# DDR_Memory.net
KiCad netlist of a schematic drawn in Altium Designer
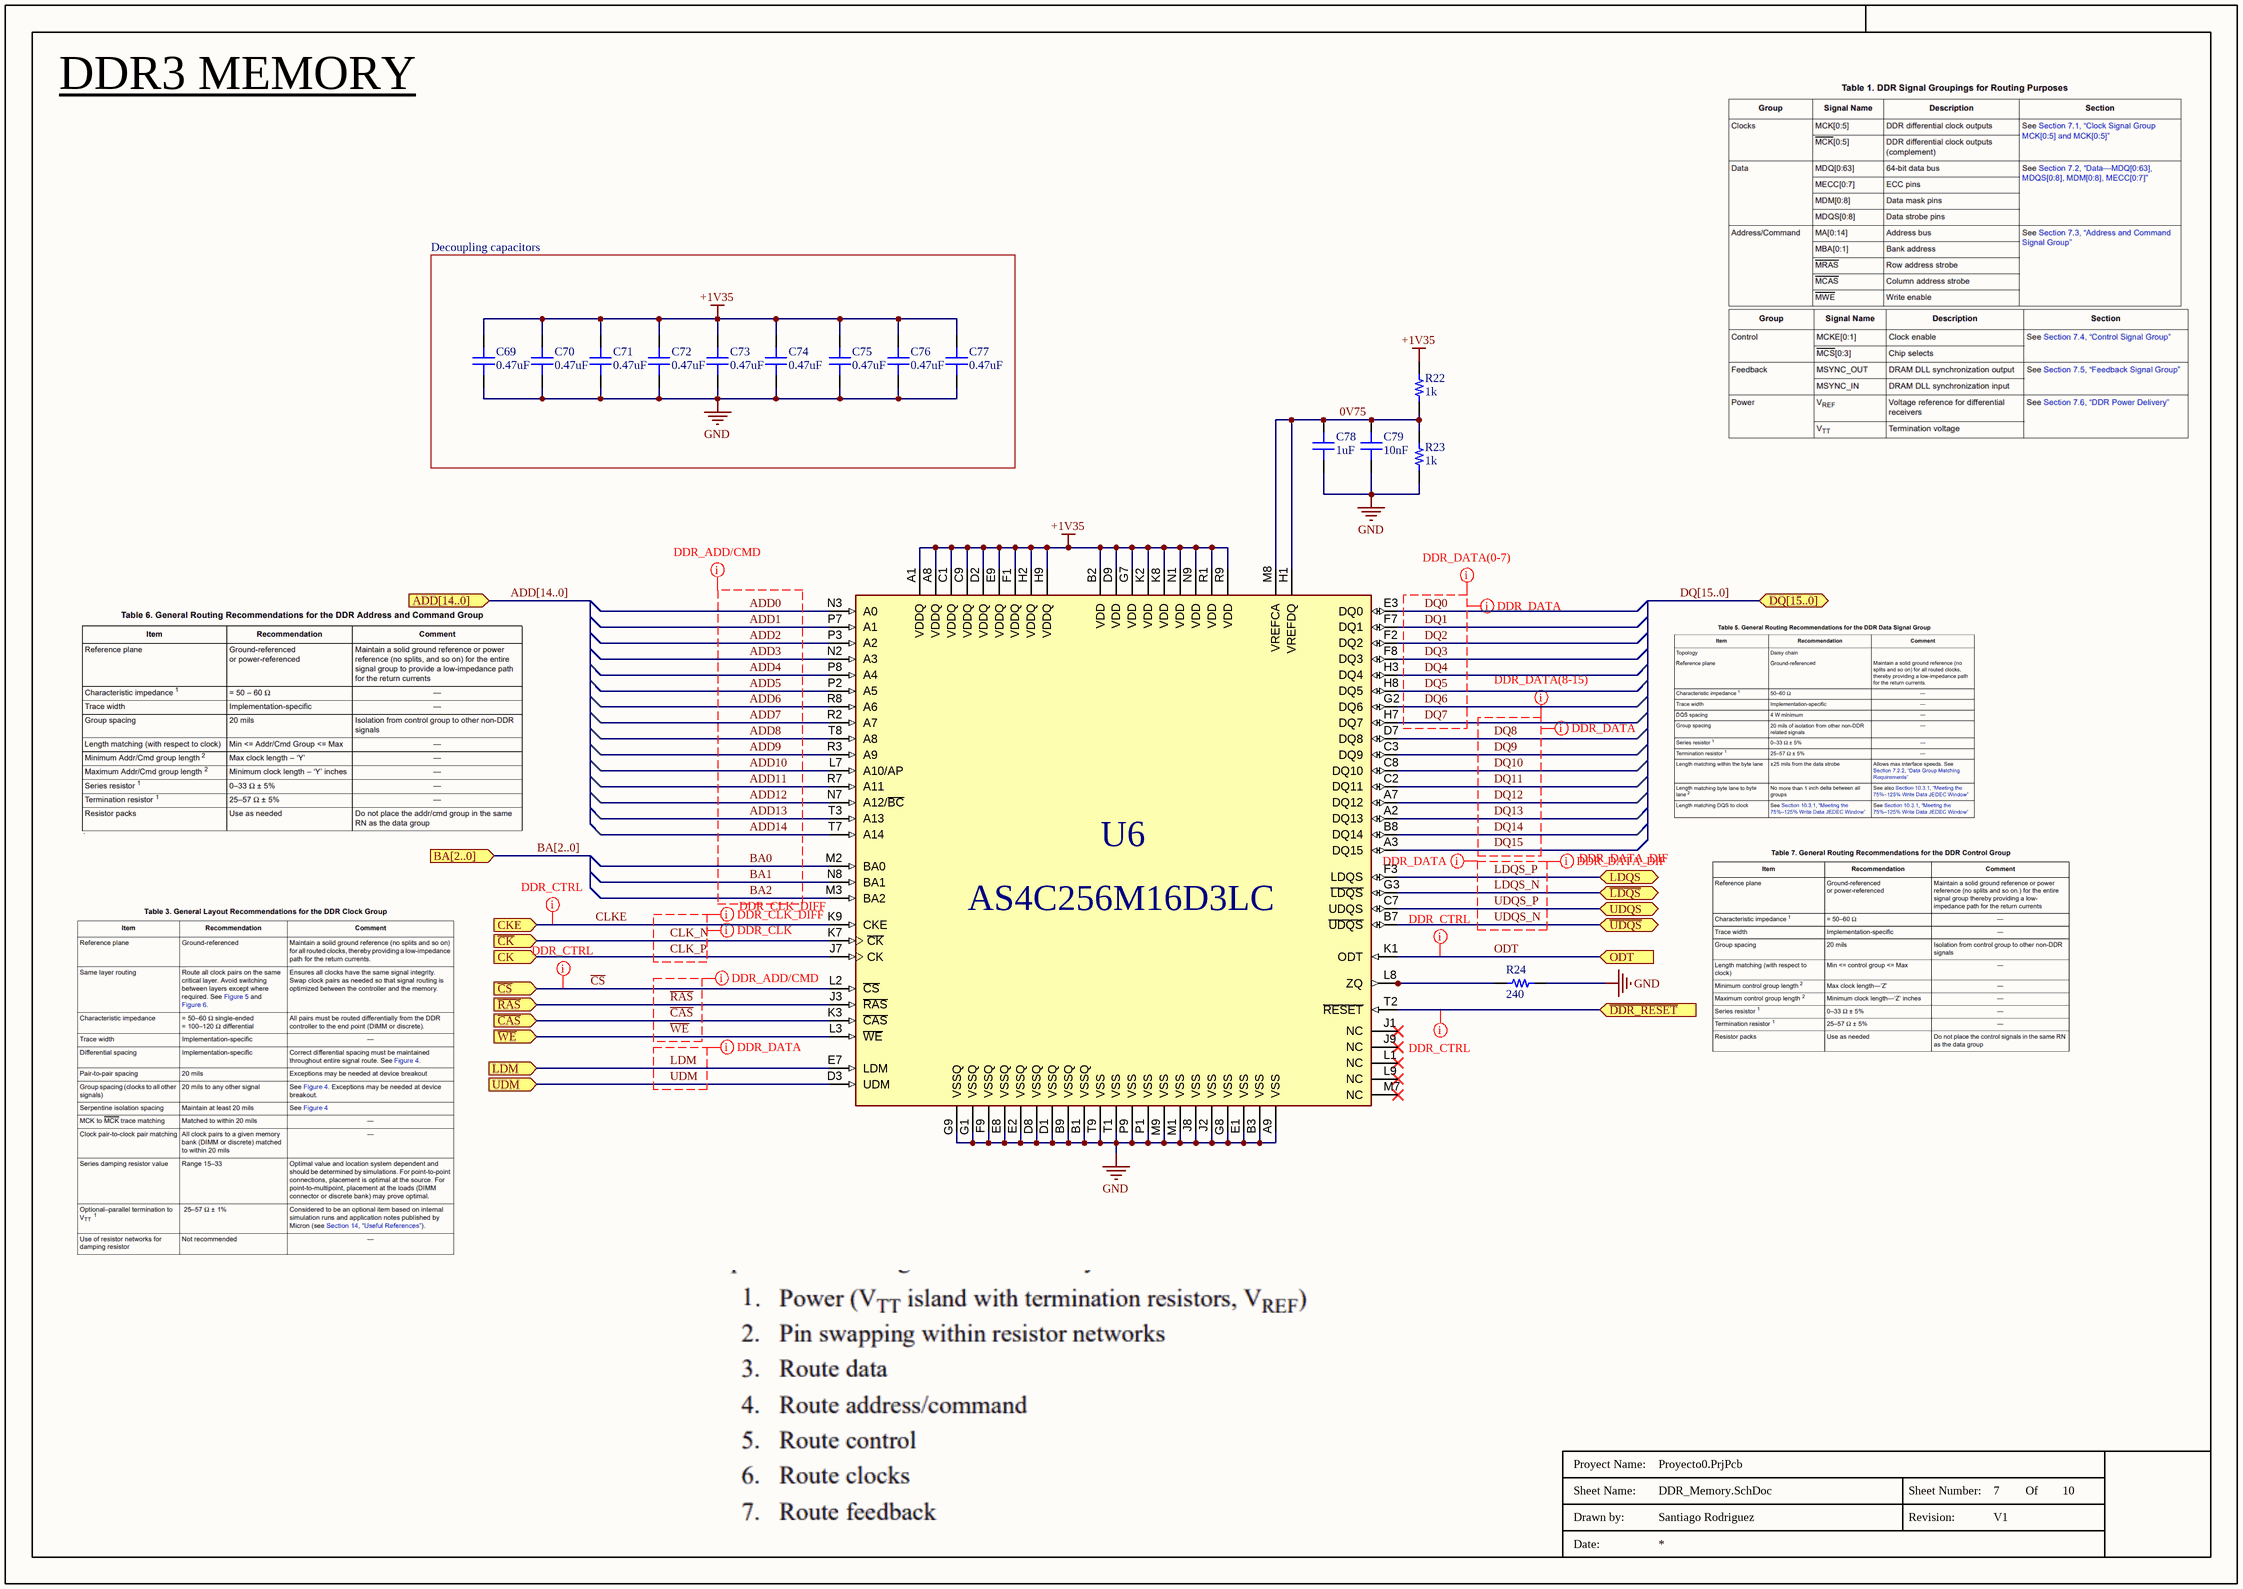
[diagram p0: DDR_Memory.SchDoc]

(export (version "E")
  (design (tool "Eeschema 10.0.6"))
  (components
    (comp (ref "C69")
      (value "0.47uF")
      (footprint "CAP0402")
      (description "CAP CER 0.47uF 10V X7R 0402 10%")
      (fields (field (name "PARTNUMBER") "C0603C474K4RAC") (field (name "TOLERANCE") "10%"))
      (libsource (lib "Pasivos") (part "C0402C474K8RAC"))
    )
    (comp (ref "C70")
      (value "0.47uF")
      (footprint "CAP0402")
      (description "CAP CER 0.47uF 10V X7R 0402 10%")
      (fields (field (name "PARTNUMBER") "C0603C474K4RAC") (field (name "TOLERANCE") "10%"))
      (libsource (lib "Pasivos") (part "C0402C474K8RAC"))
    )
    (comp (ref "C71")
      (value "0.47uF")
      (footprint "CAP0402")
      (description "CAP CER 0.47uF 10V X7R 0402 10%")
      (fields (field (name "PARTNUMBER") "C0603C474K4RAC") (field (name "TOLERANCE") "10%"))
      (libsource (lib "Pasivos") (part "C0402C474K8RAC"))
    )
    (comp (ref "C72")
      (value "0.47uF")
      (footprint "CAP0402")
      (description "CAP CER 0.47uF 10V X7R 0402 10%")
      (fields (field (name "PARTNUMBER") "C0603C474K4RAC") (field (name "TOLERANCE") "10%"))
      (libsource (lib "Pasivos") (part "C0402C474K8RAC"))
    )
    (comp (ref "C73")
      (value "0.47uF")
      (footprint "CAP0402")
      (description "CAP CER 0.47uF 10V X7R 0402 10%")
      (fields (field (name "PARTNUMBER") "C0603C474K4RAC") (field (name "TOLERANCE") "10%"))
      (libsource (lib "Pasivos") (part "C0402C474K8RAC"))
    )
    (comp (ref "C74")
      (value "0.47uF")
      (footprint "CAP0402")
      (description "CAP CER 0.47uF 10V X7R 0402 10%")
      (fields (field (name "PARTNUMBER") "C0603C474K4RAC") (field (name "TOLERANCE") "10%"))
      (libsource (lib "Pasivos") (part "C0402C474K8RAC"))
    )
    (comp (ref "C75")
      (value "0.47uF")
      (footprint "CAP0402")
      (description "CAP CER 0.47uF 10V X7R 0402 10%")
      (fields (field (name "PARTNUMBER") "C0603C474K4RAC") (field (name "TOLERANCE") "10%"))
      (libsource (lib "Pasivos") (part "C0402C474K8RAC"))
    )
    (comp (ref "C76")
      (value "0.47uF")
      (footprint "CAP0402")
      (description "CAP CER 0.47uF 10V X7R 0402 10%")
      (fields (field (name "PARTNUMBER") "C0603C474K4RAC") (field (name "TOLERANCE") "10%"))
      (libsource (lib "Pasivos") (part "C0402C474K8RAC"))
    )
    (comp (ref "C77")
      (value "0.47uF")
      (footprint "CAP0402")
      (description "CAP CER 0.47uF 10V X7R 0402 10%")
      (fields (field (name "PARTNUMBER") "C0603C474K4RAC") (field (name "TOLERANCE") "10%"))
      (libsource (lib "Pasivos") (part "C0402C474K8RAC"))
    )
    (comp (ref "C78")
      (value "1uF")
      (footprint "CAP0402")
      (description "CAP CER 1uF 16V X7R 0402 10%")
      (fields (field (name "TOLERANCE") "10%") (field (name "MANUFACTURER") "Kemet"))
      (libsource (lib "Pasivos") (part "C0402C105K4RAC"))
    )
    (comp (ref "C79")
      (value "10nF")
      (footprint "CAP0402")
      (description "CAP CER 10nF 16V X7R 0402 10%")
      (fields (field (name "TOLERANCE") "10%") (field (name "VOLTAGE") "16V"))
      (libsource (lib "Pasivos") (part "C0402C103K4RAC"))
    )
    (comp (ref "R22")
      (value "1k")
      (footprint "RES0402")
      (description "RES SMD 1K OHM 1% 0.063W 0402")
      (fields (field (name "TOLERANCE") "1%") (field (name "MANUFACTURER") "Vishay"))
      (libsource (lib "Pasivos") (part "CRCW04021K00FK"))
    )
    (comp (ref "R23")
      (value "1k")
      (footprint "RES0402")
      (description "RES SMD 1K OHM 1% 0.063W 0402")
      (fields (field (name "TOLERANCE") "1%") (field (name "MANUFACTURER") "Vishay"))
      (libsource (lib "Pasivos") (part "CRCW04021K00FK"))
    )
    (comp (ref "R24")
      (value "240")
      (footprint "RES0402")
      (description "RES SMD 240 OHM 1% 1/10W 0402")
      (fields (field (name "MANUFACTURER") "Vishay") (field (name "TOLERANCE") "1%"))
      (libsource (lib "Pasivos") (part "CRCW0402240RFK"))
    )
    (comp (ref "U6")
      (value "AS4C256M16D3LC")
      (footprint "FBGA-96")
      (description "256M x 16 bit DDR3L Synchronous DRAM (SDRAM)")
      (fields (field (name "MANUFACTURER") "Alliance Memory"))
      (libsource (lib "Integrated_Circuits") (part "AS4C256M16D3LC"))
    )
  )
  (nets
    (net (code "1") (name "+1V35") (class "Default")
      (node (ref "C69") (pin "2") (pinfunction "2_2") (pintype "passive"))
      (node (ref "C70") (pin "2") (pinfunction "2_2") (pintype "passive"))
      (node (ref "C71") (pin "2") (pinfunction "2_2") (pintype "passive"))
      (node (ref "C72") (pin "2") (pinfunction "2_2") (pintype "passive"))
      (node (ref "C73") (pin "2") (pinfunction "2_2") (pintype "passive"))
      (node (ref "C74") (pin "2") (pinfunction "2_2") (pintype "passive"))
      (node (ref "C75") (pin "2") (pinfunction "2_2") (pintype "passive"))
      (node (ref "C76") (pin "2") (pinfunction "2_2") (pintype "passive"))
      (node (ref "C77") (pin "2") (pinfunction "2_2") (pintype "passive"))
      (node (ref "R22") (pin "2") (pinfunction "2_2") (pintype "passive"))
      (node (ref "U6") (pin "A1") (pinfunction "VDDQ_A1") (pintype "power_in"))
      (node (ref "U6") (pin "A8") (pinfunction "VDDQ_A8") (pintype "power_in"))
      (node (ref "U6") (pin "B2") (pinfunction "VDD_B2") (pintype "power_in"))
      (node (ref "U6") (pin "C1") (pinfunction "VDDQ_C1") (pintype "power_in"))
      (node (ref "U6") (pin "C9") (pinfunction "VDDQ_C9") (pintype "power_in"))
      (node (ref "U6") (pin "D2") (pinfunction "VDDQ_D2") (pintype "power_in"))
      (node (ref "U6") (pin "D9") (pinfunction "VDD_D9") (pintype "power_in"))
      (node (ref "U6") (pin "E9") (pinfunction "VDDQ_E9") (pintype "power_in"))
      (node (ref "U6") (pin "F1") (pinfunction "VDDQ_F1") (pintype "power_in"))
      (node (ref "U6") (pin "G7") (pinfunction "VDD_G7") (pintype "power_in"))
      (node (ref "U6") (pin "H2") (pinfunction "VDDQ_H2") (pintype "power_in"))
      (node (ref "U6") (pin "H9") (pinfunction "VDDQ_H9") (pintype "power_in"))
      (node (ref "U6") (pin "K2") (pinfunction "VDD_K2") (pintype "power_in"))
      (node (ref "U6") (pin "K8") (pinfunction "VDD_K8") (pintype "power_in"))
      (node (ref "U6") (pin "N1") (pinfunction "VDD_N1") (pintype "power_in"))
      (node (ref "U6") (pin "N9") (pinfunction "VDD_N9") (pintype "power_in"))
      (node (ref "U6") (pin "R1") (pinfunction "VDD_R1") (pintype "power_in"))
      (node (ref "U6") (pin "R9") (pinfunction "VDD_R9") (pintype "power_in"))
    )
    (net (code "2") (name "/0V75") (class "Default")
      (node (ref "C78") (pin "2") (pinfunction "2_2") (pintype "passive"))
      (node (ref "C79") (pin "2") (pinfunction "2_2") (pintype "passive"))
      (node (ref "R22") (pin "1") (pinfunction "1_1") (pintype "passive"))
      (node (ref "R23") (pin "2") (pinfunction "2_2") (pintype "passive"))
      (node (ref "U6") (pin "H1") (pinfunction "VREFDQ_H1") (pintype "power_in"))
      (node (ref "U6") (pin "M8") (pinfunction "VREFCA_M8") (pintype "power_in"))
    )
    (net (code "3") (name "/ADD0") (class "Default")
      (node (ref "U6") (pin "N3") (pinfunction "A0_N3") (pintype "input"))
    )
    (net (code "4") (name "/ADD1") (class "Default")
      (node (ref "U6") (pin "P7") (pinfunction "A1_P7") (pintype "input"))
    )
    (net (code "5") (name "/ADD2") (class "Default")
      (node (ref "U6") (pin "P3") (pinfunction "A2_P3") (pintype "input"))
    )
    (net (code "6") (name "/ADD3") (class "Default")
      (node (ref "U6") (pin "N2") (pinfunction "A3_N2") (pintype "input"))
    )
    (net (code "7") (name "/ADD4") (class "Default")
      (node (ref "U6") (pin "P8") (pinfunction "A4_P8") (pintype "input"))
    )
    (net (code "8") (name "/ADD5") (class "Default")
      (node (ref "U6") (pin "P2") (pinfunction "A5_P2") (pintype "input"))
    )
    (net (code "9") (name "/ADD6") (class "Default")
      (node (ref "U6") (pin "R8") (pinfunction "A6_R8") (pintype "input"))
    )
    (net (code "10") (name "/ADD7") (class "Default")
      (node (ref "U6") (pin "R2") (pinfunction "A7_R2") (pintype "input"))
    )
    (net (code "11") (name "/ADD8") (class "Default")
      (node (ref "U6") (pin "T8") (pinfunction "A8_T8") (pintype "input"))
    )
    (net (code "12") (name "/ADD9") (class "Default")
      (node (ref "U6") (pin "R3") (pinfunction "A9_R3") (pintype "input"))
    )
    (net (code "13") (name "/ADD10") (class "Default")
      (node (ref "U6") (pin "L7") (pinfunction "A10/AP_L7") (pintype "input"))
    )
    (net (code "14") (name "/ADD11") (class "Default")
      (node (ref "U6") (pin "R7") (pinfunction "A11_R7") (pintype "input"))
    )
    (net (code "15") (name "/ADD12") (class "Default")
      (node (ref "U6") (pin "N7") (pinfunction "A12/~{BC}_N7") (pintype "input"))
    )
    (net (code "16") (name "/ADD13") (class "Default")
      (node (ref "U6") (pin "T3") (pinfunction "A13_T3") (pintype "input"))
    )
    (net (code "17") (name "/ADD14") (class "Default")
      (node (ref "U6") (pin "T7") (pinfunction "A14_T7") (pintype "input"))
    )
    (net (code "19") (name "/BA0") (class "Default")
      (node (ref "U6") (pin "M2") (pinfunction "BA0_M2") (pintype "input"))
    )
    (net (code "20") (name "/BA1") (class "Default")
      (node (ref "U6") (pin "N8") (pinfunction "BA1_N8") (pintype "input"))
    )
    (net (code "21") (name "/BA2") (class "Default")
      (node (ref "U6") (pin "M3") (pinfunction "BA2_M3") (pintype "input"))
    )
    (net (code "23") (name "/CLKE") (class "Default")
      (node (ref "U6") (pin "K9") (pinfunction "CKE_K9") (pintype "input"))
    )
    (net (code "24") (name "/CLK_N") (class "Default")
      (node (ref "U6") (pin "K7") (pinfunction "~{CK}_K7") (pintype "input"))
    )
    (net (code "25") (name "/CLK_P") (class "Default")
      (node (ref "U6") (pin "J7") (pinfunction "CK_J7") (pintype "input"))
    )
    (net (code "26") (name "/DQ0") (class "Default")
      (node (ref "U6") (pin "E3") (pinfunction "DQ0_E3") (pintype "bidirectional"))
    )
    (net (code "27") (name "/DQ1") (class "Default")
      (node (ref "U6") (pin "F7") (pinfunction "DQ1_F7") (pintype "bidirectional"))
    )
    (net (code "28") (name "/DQ2") (class "Default")
      (node (ref "U6") (pin "F2") (pinfunction "DQ2_F2") (pintype "bidirectional"))
    )
    (net (code "29") (name "/DQ3") (class "Default")
      (node (ref "U6") (pin "F8") (pinfunction "DQ3_F8") (pintype "bidirectional"))
    )
    (net (code "30") (name "/DQ4") (class "Default")
      (node (ref "U6") (pin "H3") (pinfunction "DQ4_H3") (pintype "bidirectional"))
    )
    (net (code "31") (name "/DQ5") (class "Default")
      (node (ref "U6") (pin "H8") (pinfunction "DQ5_H8") (pintype "bidirectional"))
    )
    (net (code "32") (name "/DQ6") (class "Default")
      (node (ref "U6") (pin "G2") (pinfunction "DQ6_G2") (pintype "bidirectional"))
    )
    (net (code "33") (name "/DQ7") (class "Default")
      (node (ref "U6") (pin "H7") (pinfunction "DQ7_H7") (pintype "bidirectional"))
    )
    (net (code "34") (name "/DQ8") (class "Default")
      (node (ref "U6") (pin "D7") (pinfunction "DQ8_D7") (pintype "bidirectional"))
    )
    (net (code "35") (name "/DQ9") (class "Default")
      (node (ref "U6") (pin "C3") (pinfunction "DQ9_C3") (pintype "bidirectional"))
    )
    (net (code "36") (name "/DQ10") (class "Default")
      (node (ref "U6") (pin "C8") (pinfunction "DQ10_C8") (pintype "bidirectional"))
    )
    (net (code "37") (name "/DQ11") (class "Default")
      (node (ref "U6") (pin "C2") (pinfunction "DQ11_C2") (pintype "bidirectional"))
    )
    (net (code "38") (name "/DQ12") (class "Default")
      (node (ref "U6") (pin "A7") (pinfunction "DQ12_A7") (pintype "bidirectional"))
    )
    (net (code "39") (name "/DQ13") (class "Default")
      (node (ref "U6") (pin "A2") (pinfunction "DQ13_A2") (pintype "bidirectional"))
    )
    (net (code "40") (name "/DQ14") (class "Default")
      (node (ref "U6") (pin "B8") (pinfunction "DQ14_B8") (pintype "bidirectional"))
    )
    (net (code "41") (name "/DQ15") (class "Default")
      (node (ref "U6") (pin "A3") (pinfunction "DQ15_A3") (pintype "bidirectional"))
    )
    (net (code "43") (name "/LDM") (class "Default")
      (node (ref "U6") (pin "E7") (pinfunction "LDM_E7") (pintype "input"))
    )
    (net (code "44") (name "/LDQS_N") (class "Default")
      (node (ref "U6") (pin "G3") (pinfunction "~{LDQS}_G3") (pintype "bidirectional"))
    )
    (net (code "45") (name "/LDQS_P") (class "Default")
      (node (ref "U6") (pin "F3") (pinfunction "LDQS_F3") (pintype "bidirectional"))
    )
    (net (code "46") (name "/ODT") (class "Default")
      (node (ref "U6") (pin "K1") (pinfunction "ODT_K1") (pintype "input"))
    )
    (net (code "47") (name "/UDM") (class "Default")
      (node (ref "U6") (pin "D3") (pinfunction "UDM_D3") (pintype "input"))
    )
    (net (code "48") (name "/UDQS_N") (class "Default")
      (node (ref "U6") (pin "B7") (pinfunction "~{UDQS}_B7") (pintype "bidirectional"))
    )
    (net (code "49") (name "/UDQS_P") (class "Default")
      (node (ref "U6") (pin "C7") (pinfunction "UDQS_C7") (pintype "bidirectional"))
    )
    (net (code "50") (name "/~{CAS}") (class "Default")
      (node (ref "U6") (pin "K3") (pinfunction "~{CAS}_K3") (pintype "input"))
    )
    (net (code "51") (name "/~{CS}") (class "Default")
      (node (ref "U6") (pin "L2") (pinfunction "~{CS}_L2") (pintype "input"))
    )
    (net (code "52") (name "/~{DDR_RESET}") (class "Default")
      (node (ref "U6") (pin "T2") (pinfunction "~{RESET}_T2") (pintype "input"))
    )
    (net (code "53") (name "/~{RAS}") (class "Default")
      (node (ref "U6") (pin "J3") (pinfunction "~{RAS}_J3") (pintype "input"))
    )
    (net (code "54") (name "/~{WE}") (class "Default")
      (node (ref "U6") (pin "L3") (pinfunction "~{WE}_L3") (pintype "input"))
    )
    (net (code "55") (name "GND") (class "Default")
      (node (ref "C69") (pin "1") (pinfunction "1_1") (pintype "passive"))
      (node (ref "C70") (pin "1") (pinfunction "1_1") (pintype "passive"))
      (node (ref "C71") (pin "1") (pinfunction "1_1") (pintype "passive"))
      (node (ref "C72") (pin "1") (pinfunction "1_1") (pintype "passive"))
      (node (ref "C73") (pin "1") (pinfunction "1_1") (pintype "passive"))
      (node (ref "C74") (pin "1") (pinfunction "1_1") (pintype "passive"))
      (node (ref "C75") (pin "1") (pinfunction "1_1") (pintype "passive"))
      (node (ref "C76") (pin "1") (pinfunction "1_1") (pintype "passive"))
      (node (ref "C77") (pin "1") (pinfunction "1_1") (pintype "passive"))
      (node (ref "C78") (pin "1") (pinfunction "1_1") (pintype "passive"))
      (node (ref "C79") (pin "1") (pinfunction "1_1") (pintype "passive"))
      (node (ref "R23") (pin "1") (pinfunction "1_1") (pintype "passive"))
      (node (ref "R24") (pin "2") (pinfunction "2_2") (pintype "passive"))
      (node (ref "U6") (pin "A9") (pinfunction "VSS_A9") (pintype "power_in"))
      (node (ref "U6") (pin "B1") (pinfunction "VSSQ_B1") (pintype "power_in"))
      (node (ref "U6") (pin "B3") (pinfunction "VSS_B3") (pintype "power_in"))
      (node (ref "U6") (pin "B9") (pinfunction "VSSQ_B9") (pintype "power_in"))
      (node (ref "U6") (pin "D1") (pinfunction "VSSQ_D1") (pintype "power_in"))
      (node (ref "U6") (pin "D8") (pinfunction "VSSQ_D8") (pintype "power_in"))
      (node (ref "U6") (pin "E1") (pinfunction "VSS_E1") (pintype "power_in"))
      (node (ref "U6") (pin "E2") (pinfunction "VSSQ_E2") (pintype "power_in"))
      (node (ref "U6") (pin "E8") (pinfunction "VSSQ_E8") (pintype "power_in"))
      (node (ref "U6") (pin "F9") (pinfunction "VSSQ_F9") (pintype "power_in"))
      (node (ref "U6") (pin "G1") (pinfunction "VSSQ_G1") (pintype "power_in"))
      (node (ref "U6") (pin "G8") (pinfunction "VSS_G8") (pintype "power_in"))
      (node (ref "U6") (pin "G9") (pinfunction "VSSQ_G9") (pintype "power_in"))
      (node (ref "U6") (pin "J2") (pinfunction "VSS_J2") (pintype "power_in"))
      (node (ref "U6") (pin "J8") (pinfunction "VSS_J8") (pintype "power_in"))
      (node (ref "U6") (pin "M1") (pinfunction "VSS_M1") (pintype "power_in"))
      (node (ref "U6") (pin "M9") (pinfunction "VSS_M9") (pintype "power_in"))
      (node (ref "U6") (pin "P1") (pinfunction "VSS_P1") (pintype "power_in"))
      (node (ref "U6") (pin "P9") (pinfunction "VSS_P9") (pintype "power_in"))
      (node (ref "U6") (pin "T1") (pinfunction "VSS_T1") (pintype "power_in"))
      (node (ref "U6") (pin "T9") (pinfunction "VSS_T9") (pintype "power_in"))
    )
    (net (code "56") (name "Net-(U6-ZQ)") (class "Default")
      (node (ref "R24") (pin "1") (pinfunction "1_1") (pintype "passive"))
      (node (ref "U6") (pin "L8") (pinfunction "ZQ_L8") (pintype "output"))
    )
    (net (code "57") (name "unconnected-(U6-NC-PadJ1)") (class "Default")
      (node (ref "U6") (pin "J1") (pinfunction "NC_J1") (pintype "passive+no_connect"))
    )
    (net (code "58") (name "unconnected-(U6-NC-PadJ9)") (class "Default")
      (node (ref "U6") (pin "J9") (pinfunction "NC_J9") (pintype "passive+no_connect"))
    )
    (net (code "59") (name "unconnected-(U6-NC-PadL1)") (class "Default")
      (node (ref "U6") (pin "L1") (pinfunction "NC_L1") (pintype "passive+no_connect"))
    )
    (net (code "60") (name "unconnected-(U6-NC-PadL9)") (class "Default")
      (node (ref "U6") (pin "L9") (pinfunction "NC_L9") (pintype "passive+no_connect"))
    )
    (net (code "61") (name "unconnected-(U6-NC-PadM7)") (class "Default")
      (node (ref "U6") (pin "M7") (pinfunction "NC_M7") (pintype "passive+no_connect"))
    )
  )
)
